# robot.net
KiCad netlist of a schematic drawn in EAGLE
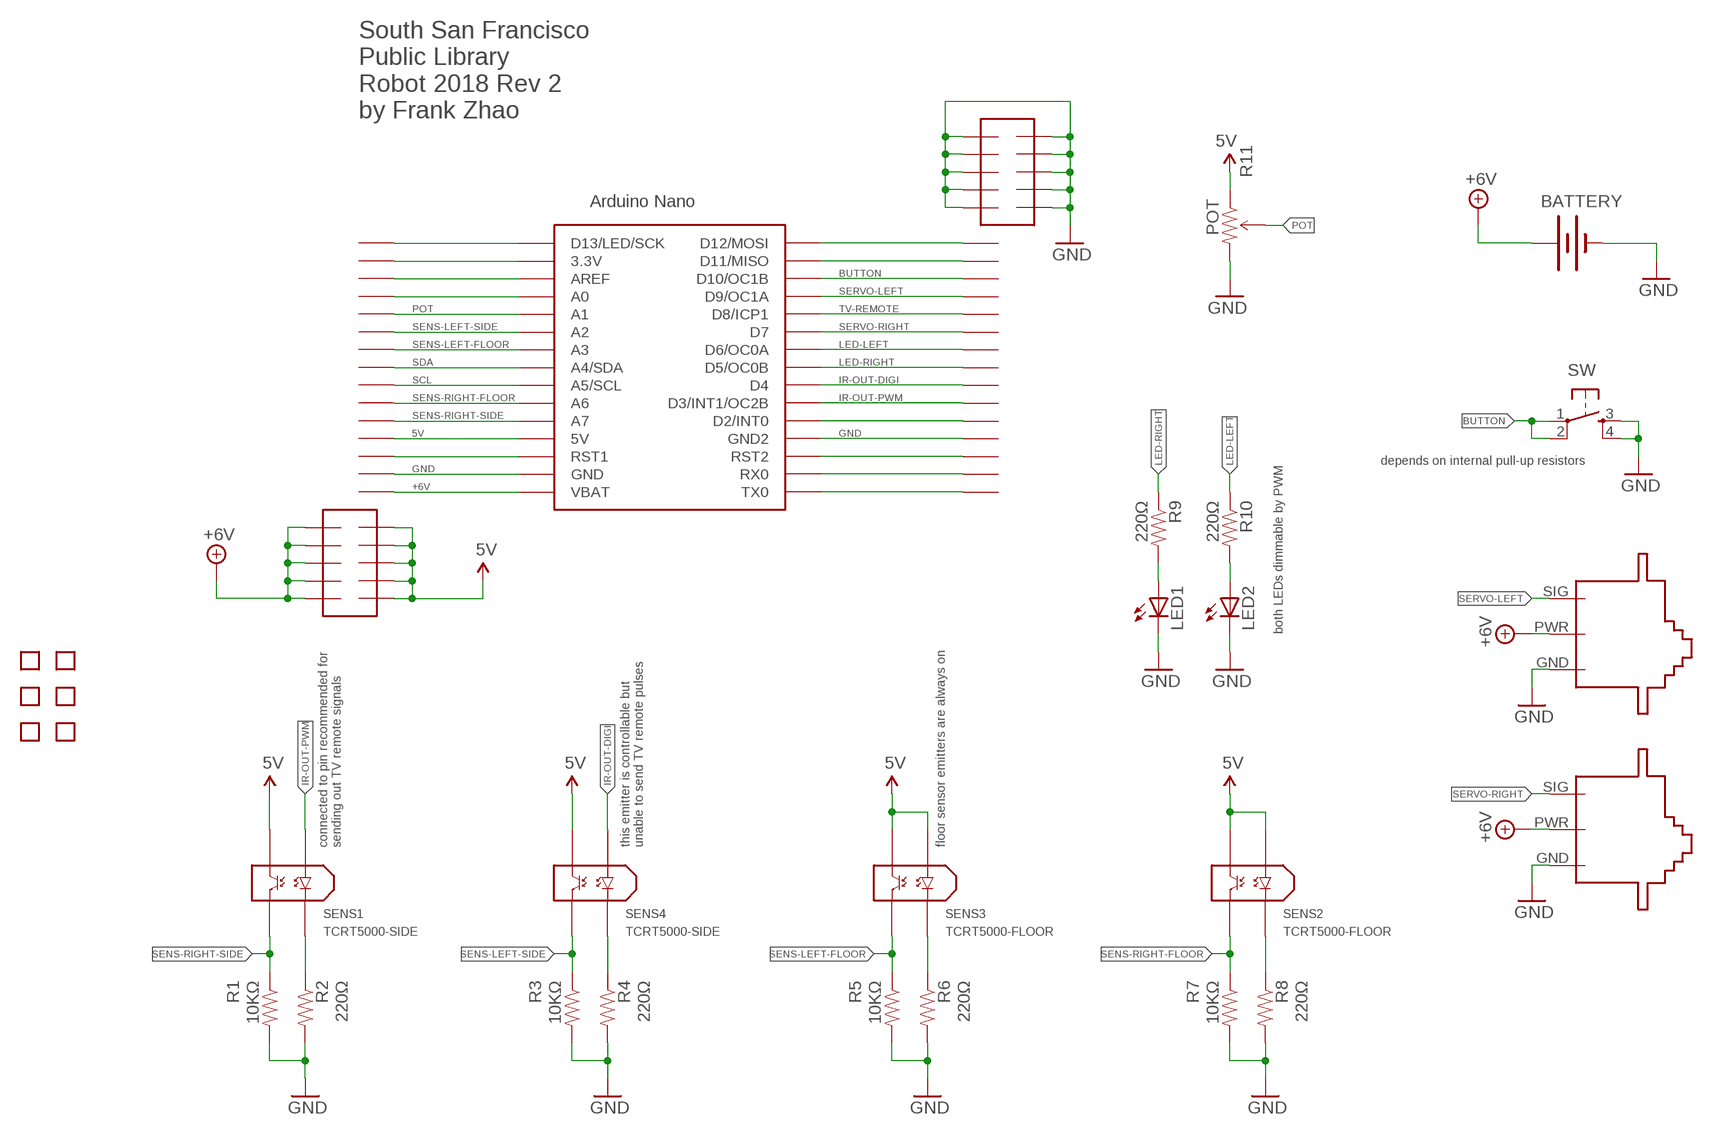
[diagram p0: schematic, sheet 1]

(export (version "E")
  (design (tool "Eeschema 10.0.6"))
  (components
    (comp (ref "BATTERY")
      (value "BATTERY-WIRE-CONN")
      (footprint "eagle-import:BATT-WIRE-CONN")
      (libsource (lib "eagle-import") (part "BATTERY-WIRE-CONN"))
    )
    (comp (ref "LED1")
      (value "LED5MM")
      (footprint "eagle-import:LED5MM")
      (libsource (lib "eagle-import") (part "LED5MM"))
    )
    (comp (ref "LED2")
      (value "LED5MM")
      (footprint "eagle-import:LED5MM")
      (libsource (lib "eagle-import") (part "LED5MM"))
    )
    (comp (ref "M1")
      (value "SERVO-FLIPPED")
      (footprint "eagle-import:SERVO-FLIPPED")
      (libsource (lib "eagle-import") (part "SERVO-FLIPPED"))
    )
    (comp (ref "M2")
      (value "SERVO-1")
      (footprint "eagle-import:SERVO")
      (libsource (lib "eagle-import") (part "SERVO-1"))
    )
    (comp (ref "R1")
      (value "10KΩ")
      (footprint "eagle-import:AXIAL-0.3")
      (libsource (lib "eagle-import") (part "RESISTORAXIAL-0.3"))
    )
    (comp (ref "R2")
      (value "220Ω")
      (footprint "eagle-import:AXIAL-0.3")
      (libsource (lib "eagle-import") (part "RESISTORAXIAL-0.3"))
    )
    (comp (ref "R3")
      (value "10KΩ")
      (footprint "eagle-import:AXIAL-0.3")
      (libsource (lib "eagle-import") (part "RESISTORAXIAL-0.3"))
    )
    (comp (ref "R4")
      (value "220Ω")
      (footprint "eagle-import:AXIAL-0.3")
      (libsource (lib "eagle-import") (part "RESISTORAXIAL-0.3"))
    )
    (comp (ref "R5")
      (value "10KΩ")
      (footprint "eagle-import:AXIAL-0.3")
      (libsource (lib "eagle-import") (part "RESISTORAXIAL-0.3"))
    )
    (comp (ref "R6")
      (value "220Ω")
      (footprint "eagle-import:AXIAL-0.3")
      (libsource (lib "eagle-import") (part "RESISTORAXIAL-0.3"))
    )
    (comp (ref "R7")
      (value "10KΩ")
      (footprint "eagle-import:AXIAL-0.3")
      (libsource (lib "eagle-import") (part "RESISTORAXIAL-0.3"))
    )
    (comp (ref "R8")
      (value "220Ω")
      (footprint "eagle-import:AXIAL-0.3")
      (libsource (lib "eagle-import") (part "RESISTORAXIAL-0.3"))
    )
    (comp (ref "R9")
      (value "220Ω")
      (footprint "eagle-import:AXIAL-0.3")
      (libsource (lib "eagle-import") (part "RESISTORAXIAL-0.3"))
    )
    (comp (ref "R10")
      (value "220Ω")
      (footprint "eagle-import:AXIAL-0.3")
      (libsource (lib "eagle-import") (part "RESISTORAXIAL-0.3"))
    )
    (comp (ref "R11")
      (value "POT")
      (footprint "eagle-import:TRIM_POT_PTH")
      (libsource (lib "eagle-import") (part "TRIMPOTPTH"))
    )
    (comp (ref "SENS1")
      (value "TCRT5000-SIDE")
      (footprint "eagle-import:TCRT5000-SIDE")
      (libsource (lib "eagle-import") (part "TCRT5000-SIDE"))
    )
    (comp (ref "SENS2")
      (value "TCRT5000-FLOOR")
      (footprint "eagle-import:TCRT5000-FLOOR")
      (libsource (lib "eagle-import") (part "TCRT5000-FLOOR"))
    )
    (comp (ref "SENS3")
      (value "TCRT5000-FLOOR")
      (footprint "eagle-import:TCRT5000-FLOOR")
      (libsource (lib "eagle-import") (part "TCRT5000-FLOOR"))
    )
    (comp (ref "SENS4")
      (value "TCRT5000-SIDE")
      (footprint "eagle-import:TCRT5000-SIDE")
      (libsource (lib "eagle-import") (part "TCRT5000-SIDE"))
    )
    (comp (ref "SW")
      (value "TAC_SWITCHPTH")
      (footprint "eagle-import:TACTILE-PTH")
      (libsource (lib "eagle-import") (part "TAC_SWITCHPTH"))
    )
    (comp (ref "U$1")
      (value "ROBOT-BODY-HOLDER")
      (footprint "eagle-import:ROBOT-BODY-HOLDER")
      (libsource (lib "eagle-import") (part "ROBOT-BODY-HOLDER"))
    )
    (comp (ref "U$8")
      (value "PROTO-AREA-MID")
      (footprint "eagle-import:PROTO-AREA-1")
      (libsource (lib "eagle-import") (part "PROTO-AREA-MID"))
    )
    (comp (ref "U$9")
      (value "TEXT-INFO")
      (footprint "eagle-import:TEXT-INFO")
      (libsource (lib "eagle-import") (part "TEXT-INFO"))
    )
    (comp (ref "U$10")
      (value "HOLE")
      (footprint "eagle-import:HOLE-2MM")
      (libsource (lib "eagle-import") (part "HOLE"))
    )
    (comp (ref "U$11")
      (value "HOLE")
      (footprint "eagle-import:HOLE-2MM")
      (libsource (lib "eagle-import") (part "HOLE"))
    )
    (comp (ref "U$12")
      (value "HOLE")
      (footprint "eagle-import:HOLE-2MM")
      (libsource (lib "eagle-import") (part "HOLE"))
    )
    (comp (ref "U$13")
      (value "HOLE")
      (footprint "eagle-import:HOLE-2MM")
      (libsource (lib "eagle-import") (part "HOLE"))
    )
    (comp (ref "U5")
      (value "NANO")
      (footprint "eagle-import:NANO")
      (libsource (lib "eagle-import") (part "NANO"))
    )
    (comp (ref "X1")
      (value "NANO-HEADER-SURROUND")
      (footprint "eagle-import:NANO-HEADER-SURROUND")
      (libsource (lib "eagle-import") (part "NANO-HEADER-SURROUND"))
    )
    (comp (ref "X2")
      (value "NANO-HEADER-SURROUND")
      (footprint "eagle-import:NANO-HEADER-SURROUND")
      (libsource (lib "eagle-import") (part "NANO-HEADER-SURROUND"))
    )
  )
  (nets
    (net (code "1") (name "+6V") (class "Default")
      (node (ref "BATTERY") (pin "POS") (pinfunction "+_POS") (pintype "power_in"))
      (node (ref "M1") (pin "PWR") (pinfunction "PWR_PWR") (pintype "bidirectional"))
      (node (ref "M2") (pin "PWR") (pinfunction "PWR_PWR") (pintype "bidirectional"))
      (node (ref "U5") (pin "RAW") (pinfunction "VBAT_RAW") (pintype "bidirectional"))
      (node (ref "X2") (pin "1") (pinfunction "1_1") (pintype "bidirectional"))
      (node (ref "X2") (pin "E1") (pinfunction "E1_E1") (pintype "bidirectional"))
      (node (ref "X2") (pin "E2") (pinfunction "E2_E2") (pintype "bidirectional"))
      (node (ref "X2") (pin "E3") (pinfunction "E3_E3") (pintype "bidirectional"))
      (node (ref "X2") (pin "E4") (pinfunction "E4_E4") (pintype "bidirectional"))
      (node (ref "X2") (pin "E5") (pinfunction "E5_E5") (pintype "bidirectional"))
    )
    (net (code "2") (name "/SCL") (class "Default")
      (node (ref "U5") (pin "A5") (pinfunction "A5/SCL_A5") (pintype "bidirectional"))
      (node (ref "X2") (pin "7") (pinfunction "7_7") (pintype "bidirectional"))
    )
    (net (code "3") (name "/SDA") (class "Default")
      (node (ref "U5") (pin "A4") (pinfunction "A4/SDA_A4") (pintype "bidirectional"))
      (node (ref "X2") (pin "8") (pinfunction "8_8") (pintype "bidirectional"))
    )
    (net (code "4") (name "/TV-REMOTE") (class "Default")
      (node (ref "U5") (pin "D8") (pinfunction "D8/ICP1_D8") (pintype "bidirectional"))
      (node (ref "X1") (pin "5") (pinfunction "5_5") (pintype "bidirectional"))
    )
    (net (code "5") (name "5V") (class "Default")
      (node (ref "R11") (pin "1") (pinfunction "CCW_1") (pintype "passive"))
      (node (ref "SENS1") (pin "COL") (pinfunction "COL_COL") (pintype "bidirectional"))
      (node (ref "SENS2") (pin "AN") (pinfunction "AN_AN") (pintype "bidirectional"))
      (node (ref "SENS2") (pin "COL") (pinfunction "COL_COL") (pintype "bidirectional"))
      (node (ref "SENS3") (pin "AN") (pinfunction "AN_AN") (pintype "bidirectional"))
      (node (ref "SENS3") (pin "COL") (pinfunction "COL_COL") (pintype "bidirectional"))
      (node (ref "SENS4") (pin "COL") (pinfunction "COL_COL") (pintype "bidirectional"))
      (node (ref "U5") (pin "5V") (pinfunction "5V_5V") (pintype "bidirectional"))
      (node (ref "X2") (pin "4") (pinfunction "4_4") (pintype "bidirectional"))
      (node (ref "X2") (pin "E10") (pinfunction "E10_E10") (pintype "bidirectional"))
      (node (ref "X2") (pin "E6") (pinfunction "E6_E6") (pintype "bidirectional"))
      (node (ref "X2") (pin "E7") (pinfunction "E7_E7") (pintype "bidirectional"))
      (node (ref "X2") (pin "E8") (pinfunction "E8_E8") (pintype "bidirectional"))
      (node (ref "X2") (pin "E9") (pinfunction "E9_E9") (pintype "bidirectional"))
    )
    (net (code "6") (name "BUTTON") (class "Default")
      (node (ref "SW") (pin "1") (pinfunction "1_1") (pintype "passive"))
      (node (ref "SW") (pin "2") (pinfunction "2_2") (pintype "passive"))
      (node (ref "U5") (pin "D10") (pinfunction "D10/OC1B_D10") (pintype "bidirectional"))
      (node (ref "X1") (pin "3") (pinfunction "3_3") (pintype "bidirectional"))
    )
    (net (code "7") (name "GND") (class "Default")
      (node (ref "BATTERY") (pin "NEG") (pinfunction "-_NEG") (pintype "power_in"))
      (node (ref "LED1") (pin "K") (pinfunction "C_K") (pintype "passive"))
      (node (ref "LED2") (pin "K") (pinfunction "C_K") (pintype "passive"))
      (node (ref "M1") (pin "GND") (pinfunction "GND_GND") (pintype "bidirectional"))
      (node (ref "M2") (pin "GND") (pinfunction "GND_GND") (pintype "bidirectional"))
      (node (ref "R1") (pin "P$2") (pinfunction "2_P$2") (pintype "passive"))
      (node (ref "R11") (pin "3") (pinfunction "CW_3") (pintype "passive"))
      (node (ref "R2") (pin "P$2") (pinfunction "2_P$2") (pintype "passive"))
      (node (ref "R3") (pin "P$2") (pinfunction "2_P$2") (pintype "passive"))
      (node (ref "R4") (pin "P$2") (pinfunction "2_P$2") (pintype "passive"))
      (node (ref "R5") (pin "P$2") (pinfunction "2_P$2") (pintype "passive"))
      (node (ref "R6") (pin "P$2") (pinfunction "2_P$2") (pintype "passive"))
      (node (ref "R7") (pin "P$2") (pinfunction "2_P$2") (pintype "passive"))
      (node (ref "R8") (pin "P$2") (pinfunction "2_P$2") (pintype "passive"))
      (node (ref "SW") (pin "3") (pinfunction "3_3") (pintype "passive"))
      (node (ref "SW") (pin "4") (pinfunction "4_4") (pintype "passive"))
      (node (ref "U5") (pin "GND") (pinfunction "GND_GND") (pintype "bidirectional"))
      (node (ref "U5") (pin "GND1") (pinfunction "GND2_GND1") (pintype "bidirectional"))
      (node (ref "X1") (pin "12") (pinfunction "12_12") (pintype "bidirectional"))
      (node (ref "X1") (pin "E1") (pinfunction "E1_E1") (pintype "bidirectional"))
      (node (ref "X1") (pin "E10") (pinfunction "E10_E10") (pintype "bidirectional"))
      (node (ref "X1") (pin "E2") (pinfunction "E2_E2") (pintype "bidirectional"))
      (node (ref "X1") (pin "E3") (pinfunction "E3_E3") (pintype "bidirectional"))
      (node (ref "X1") (pin "E4") (pinfunction "E4_E4") (pintype "bidirectional"))
      (node (ref "X1") (pin "E5") (pinfunction "E5_E5") (pintype "bidirectional"))
      (node (ref "X1") (pin "E6") (pinfunction "E6_E6") (pintype "bidirectional"))
      (node (ref "X1") (pin "E7") (pinfunction "E7_E7") (pintype "bidirectional"))
      (node (ref "X1") (pin "E8") (pinfunction "E8_E8") (pintype "bidirectional"))
      (node (ref "X1") (pin "E9") (pinfunction "E9_E9") (pintype "bidirectional"))
      (node (ref "X2") (pin "2") (pinfunction "2_2") (pintype "bidirectional"))
    )
    (net (code "8") (name "IR-OUT-DIGI") (class "Default")
      (node (ref "SENS4") (pin "AN") (pinfunction "AN_AN") (pintype "bidirectional"))
      (node (ref "U5") (pin "D4") (pinfunction "D4_D4") (pintype "bidirectional"))
      (node (ref "X1") (pin "9") (pinfunction "9_9") (pintype "bidirectional"))
    )
    (net (code "9") (name "IR-OUT-PWM") (class "Default")
      (node (ref "SENS1") (pin "AN") (pinfunction "AN_AN") (pintype "bidirectional"))
      (node (ref "U5") (pin "D3") (pinfunction "D3/INT1/OC2B_D3") (pintype "bidirectional"))
      (node (ref "X1") (pin "10") (pinfunction "10_10") (pintype "bidirectional"))
    )
    (net (code "10") (name "LED-LEFT") (class "Default")
      (node (ref "R10") (pin "P$1") (pinfunction "1_P$1") (pintype "passive"))
      (node (ref "U5") (pin "D6") (pinfunction "D6/OC0A_D6") (pintype "bidirectional"))
      (node (ref "X1") (pin "7") (pinfunction "7_7") (pintype "bidirectional"))
    )
    (net (code "11") (name "LED-RIGHT") (class "Default")
      (node (ref "R9") (pin "P$1") (pinfunction "1_P$1") (pintype "passive"))
      (node (ref "U5") (pin "D5") (pinfunction "D5/OC0B_D5") (pintype "bidirectional"))
      (node (ref "X1") (pin "8") (pinfunction "8_8") (pintype "bidirectional"))
    )
    (net (code "12") (name "Net-(R2-1)") (class "Default")
      (node (ref "R2") (pin "P$1") (pinfunction "1_P$1") (pintype "passive"))
      (node (ref "SENS1") (pin "CAT") (pinfunction "CAT_CAT") (pintype "bidirectional"))
    )
    (net (code "13") (name "Net-(R4-1)") (class "Default")
      (node (ref "R4") (pin "P$1") (pinfunction "1_P$1") (pintype "passive"))
      (node (ref "SENS4") (pin "CAT") (pinfunction "CAT_CAT") (pintype "bidirectional"))
    )
    (net (code "14") (name "Net-(R6-1)") (class "Default")
      (node (ref "R6") (pin "P$1") (pinfunction "1_P$1") (pintype "passive"))
      (node (ref "SENS3") (pin "CAT") (pinfunction "CAT_CAT") (pintype "bidirectional"))
    )
    (net (code "15") (name "Net-(R8-1)") (class "Default")
      (node (ref "R8") (pin "P$1") (pinfunction "1_P$1") (pintype "passive"))
      (node (ref "SENS2") (pin "CAT") (pinfunction "CAT_CAT") (pintype "bidirectional"))
    )
    (net (code "16") (name "Net-(R9-2)") (class "Default")
      (node (ref "LED1") (pin "A") (pinfunction "A_A") (pintype "passive"))
      (node (ref "R9") (pin "P$2") (pinfunction "2_P$2") (pintype "passive"))
    )
    (net (code "17") (name "Net-(R10-2)") (class "Default")
      (node (ref "LED2") (pin "A") (pinfunction "A_A") (pintype "passive"))
      (node (ref "R10") (pin "P$2") (pinfunction "2_P$2") (pintype "passive"))
    )
    (net (code "18") (name "Net-(U5-D2{slash}INT0)") (class "Default")
      (node (ref "U5") (pin "D2") (pinfunction "D2/INT0_D2") (pintype "bidirectional"))
      (node (ref "X1") (pin "11") (pinfunction "11_11") (pintype "bidirectional"))
    )
    (net (code "19") (name "Net-(U5-D11{slash}MISO)") (class "Default")
      (node (ref "U5") (pin "D11") (pinfunction "D11/MISO_D11") (pintype "bidirectional"))
      (node (ref "X1") (pin "2") (pinfunction "2_2") (pintype "bidirectional"))
    )
    (net (code "20") (name "Net-(U5-D12{slash}MOSI)") (class "Default")
      (node (ref "U5") (pin "D12") (pinfunction "D12/MOSI_D12") (pintype "bidirectional"))
      (node (ref "X1") (pin "1") (pinfunction "1_1") (pintype "bidirectional"))
    )
    (net (code "21") (name "Net-(U5-D13{slash}LED{slash}SCK)") (class "Default")
      (node (ref "U5") (pin "D13") (pinfunction "D13/LED/SCK_D13") (pintype "bidirectional"))
      (node (ref "X2") (pin "15") (pinfunction "15_15") (pintype "bidirectional"))
    )
    (net (code "22") (name "Net-(U5-Pad3.3V)") (class "Default")
      (node (ref "U5") (pin "3.3V") (pinfunction "3.3V_3.3V") (pintype "bidirectional"))
      (node (ref "X2") (pin "14") (pinfunction "14_14") (pintype "bidirectional"))
    )
    (net (code "23") (name "Net-(U5-PadA0)") (class "Default")
      (node (ref "U5") (pin "A0") (pinfunction "A0_A0") (pintype "bidirectional"))
      (node (ref "X2") (pin "12") (pinfunction "12_12") (pintype "bidirectional"))
    )
    (net (code "24") (name "Net-(U5-PadAREF)") (class "Default")
      (node (ref "U5") (pin "AREF") (pinfunction "AREF_AREF") (pintype "bidirectional"))
      (node (ref "X2") (pin "13") (pinfunction "13_13") (pintype "bidirectional"))
    )
    (net (code "25") (name "Net-(U5-PadRX0)") (class "Default")
      (node (ref "U5") (pin "RX0") (pinfunction "RX0_RX0") (pintype "bidirectional"))
      (node (ref "X1") (pin "14") (pinfunction "14_14") (pintype "bidirectional"))
    )
    (net (code "26") (name "Net-(U5-PadTX0)") (class "Default")
      (node (ref "U5") (pin "TX0") (pinfunction "TX0_TX0") (pintype "bidirectional"))
      (node (ref "X1") (pin "15") (pinfunction "15_15") (pintype "bidirectional"))
    )
    (net (code "27") (name "Net-(U5-RST1)") (class "Default")
      (node (ref "U5") (pin "RST") (pinfunction "RST1_RST") (pintype "bidirectional"))
      (node (ref "X2") (pin "3") (pinfunction "3_3") (pintype "bidirectional"))
    )
    (net (code "28") (name "Net-(U5-RST2)") (class "Default")
      (node (ref "U5") (pin "RST1") (pinfunction "RST2_RST1") (pintype "bidirectional"))
      (node (ref "X1") (pin "13") (pinfunction "13_13") (pintype "bidirectional"))
    )
    (net (code "29") (name "POT") (class "Default")
      (node (ref "R11") (pin "2") (pinfunction "WIPER_2") (pintype "passive"))
      (node (ref "U5") (pin "A1") (pinfunction "A1_A1") (pintype "bidirectional"))
      (node (ref "X2") (pin "11") (pinfunction "11_11") (pintype "bidirectional"))
    )
    (net (code "30") (name "SENS-LEFT-FLOOR") (class "Default")
      (node (ref "R5") (pin "P$1") (pinfunction "1_P$1") (pintype "passive"))
      (node (ref "SENS3") (pin "EM") (pinfunction "EM_EM") (pintype "bidirectional"))
      (node (ref "U5") (pin "A3") (pinfunction "A3_A3") (pintype "bidirectional"))
      (node (ref "X2") (pin "9") (pinfunction "9_9") (pintype "bidirectional"))
    )
    (net (code "31") (name "SENS-LEFT-SIDE") (class "Default")
      (node (ref "R3") (pin "P$1") (pinfunction "1_P$1") (pintype "passive"))
      (node (ref "SENS4") (pin "EM") (pinfunction "EM_EM") (pintype "bidirectional"))
      (node (ref "U5") (pin "A2") (pinfunction "A2_A2") (pintype "bidirectional"))
      (node (ref "X2") (pin "10") (pinfunction "10_10") (pintype "bidirectional"))
    )
    (net (code "32") (name "SENS-RIGHT-FLOOR") (class "Default")
      (node (ref "R7") (pin "P$1") (pinfunction "1_P$1") (pintype "passive"))
      (node (ref "SENS2") (pin "EM") (pinfunction "EM_EM") (pintype "bidirectional"))
      (node (ref "U5") (pin "A6") (pinfunction "A6_A6") (pintype "bidirectional"))
      (node (ref "X2") (pin "6") (pinfunction "6_6") (pintype "bidirectional"))
    )
    (net (code "33") (name "SENS-RIGHT-SIDE") (class "Default")
      (node (ref "R1") (pin "P$1") (pinfunction "1_P$1") (pintype "passive"))
      (node (ref "SENS1") (pin "EM") (pinfunction "EM_EM") (pintype "bidirectional"))
      (node (ref "U5") (pin "A7") (pinfunction "A7_A7") (pintype "bidirectional"))
      (node (ref "X2") (pin "5") (pinfunction "5_5") (pintype "bidirectional"))
    )
    (net (code "34") (name "SERVO-LEFT") (class "Default")
      (node (ref "M2") (pin "SIG") (pinfunction "SIG_SIG") (pintype "bidirectional"))
      (node (ref "U5") (pin "D9") (pinfunction "D9/OC1A_D9") (pintype "bidirectional"))
      (node (ref "X1") (pin "4") (pinfunction "4_4") (pintype "bidirectional"))
    )
    (net (code "35") (name "SERVO-RIGHT") (class "Default")
      (node (ref "M1") (pin "SIG") (pinfunction "SIG_SIG") (pintype "bidirectional"))
      (node (ref "U5") (pin "D7") (pinfunction "D7_D7") (pintype "bidirectional"))
      (node (ref "X1") (pin "6") (pinfunction "6_6") (pintype "bidirectional"))
    )
  )
)
